# Imu_shield_v1.net
KiCad netlist of a schematic drawn in EAGLE
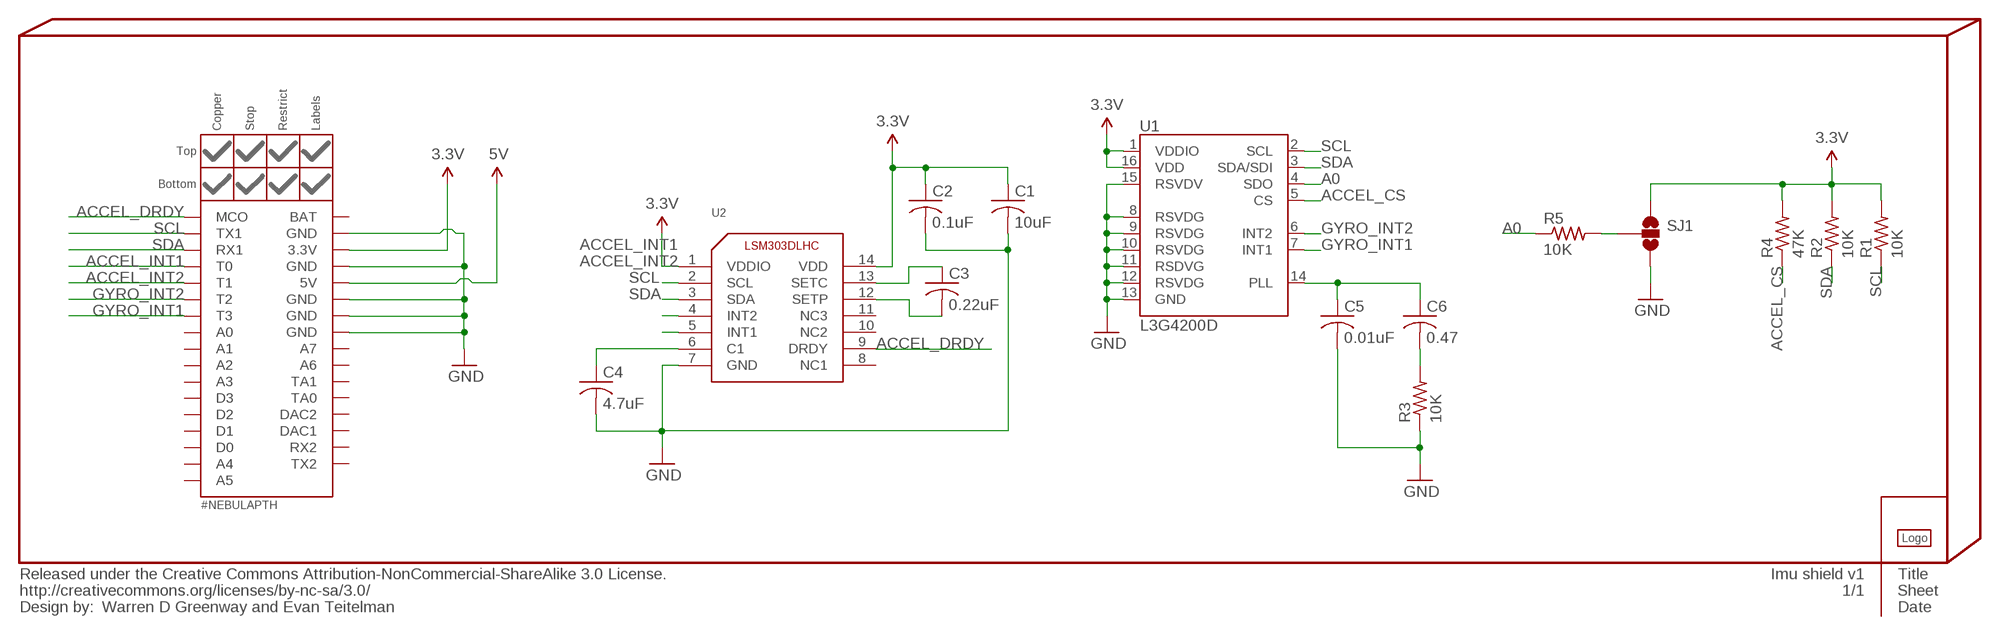
[diagram p0: schematic, sheet 1]

(export (version "E")
  (design (tool "Eeschema 10.0.6"))
  (components
    (comp (ref "C1")
      (value "10uF")
      (footprint "eagle-import:C0805")
      (libsource (lib "eagle-import") (part "C-USC0805"))
    )
    (comp (ref "C2")
      (value "0.1uF")
      (footprint "eagle-import:C0402")
      (libsource (lib "eagle-import") (part "C-USC0402"))
    )
    (comp (ref "C3")
      (value "0.22uF")
      (footprint "eagle-import:C0402")
      (libsource (lib "eagle-import") (part "C-USC0402"))
    )
    (comp (ref "C4")
      (value "4.7uF")
      (footprint "eagle-import:C0402")
      (libsource (lib "eagle-import") (part "C-USC0402"))
    )
    (comp (ref "C5")
      (value "0.01uF")
      (footprint "eagle-import:C0402")
      (libsource (lib "eagle-import") (part "C-USC0402"))
    )
    (comp (ref "C6")
      (value "0.47")
      (footprint "eagle-import:C0402")
      (libsource (lib "eagle-import") (part "C-USC0402"))
    )
    (comp (ref "INFO2")
      (value "Warren D Greenway and Evan Teitelman")
      (footprint "eagle-import:%CC-NC-SA")
      (libsource (lib "eagle-import") (part "%CC-NC-SA"))
    )
    (comp (ref "LOGO1")
      (value "#PYGMYLOGONORMAL")
      (footprint "eagle-import:#PYGMYLOGO")
      (libsource (lib "eagle-import") (part "#PYGMYLOGOLARGE"))
    )
    (comp (ref "NEBULA1")
      (value "#NEBULAPTH")
      (footprint "eagle-import:#NEBULA-PTH")
      (libsource (lib "eagle-import") (part "#NEBULAPTH"))
    )
    (comp (ref "NEBULAPART1")
      (value "#NEBULA-PARTLABELS-TOP")
      (footprint "eagle-import:#NEBULA-LABELS-TOP")
      (libsource (lib "eagle-import") (part "#NEBULA-PARTLABELS-TOP"))
    )
    (comp (ref "R1")
      (value "10K")
      (footprint "eagle-import:R0402")
      (libsource (lib "eagle-import") (part "R-US_R0402"))
    )
    (comp (ref "R2")
      (value "10K")
      (footprint "eagle-import:R0402")
      (libsource (lib "eagle-import") (part "R-US_R0402"))
    )
    (comp (ref "R3")
      (value "10K")
      (footprint "eagle-import:R0402")
      (libsource (lib "eagle-import") (part "R-US_R0402"))
    )
    (comp (ref "R4")
      (value "47K")
      (footprint "eagle-import:R0402")
      (libsource (lib "eagle-import") (part "R-US_R0402"))
    )
    (comp (ref "R5")
      (value "10K")
      (footprint "eagle-import:R0402")
      (libsource (lib "eagle-import") (part "R-US_R0402"))
    )
    (comp (ref "SJ1")
      (value "SOLDERJUMPER_2WAYPASTE1&2")
      (footprint "eagle-import:SJ_3_PASTE1&2")
      (libsource (lib "eagle-import") (part "SOLDERJUMPER_2WAYPASTE1&2"))
    )
    (comp (ref "U1")
      (value "L3G4200D")
      (footprint "eagle-import:LGA16-4X4")
      (libsource (lib "eagle-import") (part "L3G4200D"))
    )
    (comp (ref "U2")
      (value "FREESCALE-LSM303DLHC")
      (footprint "eagle-import:LGA14")
      (libsource (lib "eagle-import") (part "FREESCALE-LSM303DLHC"))
    )
  )
  (nets
    (net (code "1") (name "/A0") (class "Default")
      (node (ref "R5") (pin "1") (pinfunction "1_1") (pintype "passive"))
      (node (ref "U1") (pin "4") (pinfunction "SDO_4") (pintype "bidirectional"))
    )
    (net (code "2") (name "/ACCEL_CS") (class "Default")
      (node (ref "R4") (pin "1") (pinfunction "1_1") (pintype "passive"))
      (node (ref "U1") (pin "5") (pinfunction "CS_5") (pintype "bidirectional"))
    )
    (net (code "3") (name "/ACCEL_DRDY") (class "Default")
      (node (ref "NEBULA1") (pin "MCO") (pinfunction "MCO_MCO") (pintype "bidirectional"))
      (node (ref "U2") (pin "9") (pinfunction "DRDY_9") (pintype "bidirectional"))
    )
    (net (code "4") (name "/ACCEL_INT1") (class "Default")
      (node (ref "NEBULA1") (pin "T0") (pinfunction "T0_T0") (pintype "bidirectional"))
      (node (ref "U2") (pin "4") (pinfunction "INT2_4") (pintype "bidirectional"))
    )
    (net (code "5") (name "/ACCEL_INT2") (class "Default")
      (node (ref "NEBULA1") (pin "T1") (pinfunction "T1_T1") (pintype "bidirectional"))
      (node (ref "U2") (pin "5") (pinfunction "INT1_5") (pintype "bidirectional"))
    )
    (net (code "6") (name "/GYRO_INT1") (class "Default")
      (node (ref "NEBULA1") (pin "T3") (pinfunction "T3_T3") (pintype "bidirectional"))
      (node (ref "U1") (pin "7") (pinfunction "INT1_7") (pintype "bidirectional"))
    )
    (net (code "7") (name "/GYRO_INT2") (class "Default")
      (node (ref "NEBULA1") (pin "T2") (pinfunction "T2_T2") (pintype "bidirectional"))
      (node (ref "U1") (pin "6") (pinfunction "INT2_6") (pintype "bidirectional"))
    )
    (net (code "8") (name "/SCL") (class "Default")
      (node (ref "NEBULA1") (pin "COM1_TX") (pinfunction "TX1_COM1_TX") (pintype "bidirectional"))
      (node (ref "R1") (pin "1") (pinfunction "1_1") (pintype "passive"))
      (node (ref "U1") (pin "2") (pinfunction "SCL_2") (pintype "bidirectional"))
      (node (ref "U2") (pin "2") (pinfunction "SCL_2") (pintype "bidirectional"))
    )
    (net (code "9") (name "/SDA") (class "Default")
      (node (ref "NEBULA1") (pin "COM1_RX") (pinfunction "RX1_COM1_RX") (pintype "bidirectional"))
      (node (ref "R2") (pin "1") (pinfunction "1_1") (pintype "passive"))
      (node (ref "U1") (pin "3") (pinfunction "SDA/SDI_3") (pintype "bidirectional"))
      (node (ref "U2") (pin "3") (pinfunction "SDA_3") (pintype "bidirectional"))
    )
    (net (code "10") (name "@3.3V") (class "Default")
      (node (ref "C1") (pin "1") (pinfunction "1_1") (pintype "passive"))
      (node (ref "C2") (pin "1") (pinfunction "1_1") (pintype "passive"))
      (node (ref "NEBULA1") (pin "3.3V") (pinfunction "3.3V_3.3V") (pintype "bidirectional"))
      (node (ref "R1") (pin "2") (pinfunction "2_2") (pintype "passive"))
      (node (ref "R2") (pin "2") (pinfunction "2_2") (pintype "passive"))
      (node (ref "R4") (pin "2") (pinfunction "2_2") (pintype "passive"))
      (node (ref "SJ1") (pin "1") (pinfunction "1_1") (pintype "passive"))
      (node (ref "U1") (pin "1") (pinfunction "VDDIO_1") (pintype "bidirectional"))
      (node (ref "U1") (pin "16") (pinfunction "VDD_16") (pintype "bidirectional"))
      (node (ref "U2") (pin "1") (pinfunction "VDDIO_1") (pintype "bidirectional"))
      (node (ref "U2") (pin "14") (pinfunction "VDD_14") (pintype "bidirectional"))
    )
    (net (code "11") (name "@5V") (class "Default")
      (node (ref "NEBULA1") (pin "5V") (pinfunction "5V_5V") (pintype "bidirectional"))
    )
    (net (code "12") (name "@GND") (class "Default")
      (node (ref "C1") (pin "2") (pinfunction "2_2") (pintype "passive"))
      (node (ref "C2") (pin "2") (pinfunction "2_2") (pintype "passive"))
      (node (ref "C4") (pin "2") (pinfunction "2_2") (pintype "passive"))
      (node (ref "C5") (pin "2") (pinfunction "2_2") (pintype "passive"))
      (node (ref "NEBULA1") (pin "GND1") (pinfunction "GND_GND1") (pintype "bidirectional"))
      (node (ref "NEBULA1") (pin "GND2") (pinfunction "GND_GND2") (pintype "bidirectional"))
      (node (ref "NEBULA1") (pin "GND3") (pinfunction "GND_GND3") (pintype "bidirectional"))
      (node (ref "NEBULA1") (pin "GND4") (pinfunction "GND_GND4") (pintype "bidirectional"))
      (node (ref "NEBULA1") (pin "GND5") (pinfunction "GND_GND5") (pintype "bidirectional"))
      (node (ref "R3") (pin "1") (pinfunction "1_1") (pintype "passive"))
      (node (ref "SJ1") (pin "3") (pinfunction "3_3") (pintype "passive"))
      (node (ref "U1") (pin "10") (pinfunction "RSVDG_10") (pintype "bidirectional"))
      (node (ref "U1") (pin "11") (pinfunction "RSDVG_11") (pintype "bidirectional"))
      (node (ref "U1") (pin "12") (pinfunction "RSVDG_12") (pintype "bidirectional"))
      (node (ref "U1") (pin "13") (pinfunction "GND_13") (pintype "bidirectional"))
      (node (ref "U1") (pin "15") (pinfunction "RSVDV_15") (pintype "bidirectional"))
      (node (ref "U1") (pin "8") (pinfunction "RSVDG_8") (pintype "bidirectional"))
      (node (ref "U1") (pin "9") (pinfunction "RSVDG_9") (pintype "bidirectional"))
      (node (ref "U2") (pin "7") (pinfunction "GND_7") (pintype "bidirectional"))
    )
    (net (code "13") (name "Net-(C6-Pad2)") (class "Default")
      (node (ref "C6") (pin "2") (pinfunction "2_2") (pintype "passive"))
      (node (ref "R3") (pin "2") (pinfunction "2_2") (pintype "passive"))
    )
    (net (code "14") (name "Net-(R5-Pad2)") (class "Default")
      (node (ref "R5") (pin "2") (pinfunction "2_2") (pintype "passive"))
      (node (ref "SJ1") (pin "2") (pinfunction "2_2") (pintype "passive"))
    )
    (net (code "15") (name "Net-(U1-PLL)") (class "Default")
      (node (ref "C5") (pin "1") (pinfunction "1_1") (pintype "passive"))
      (node (ref "C6") (pin "1") (pinfunction "1_1") (pintype "passive"))
      (node (ref "U1") (pin "14") (pinfunction "PLL_14") (pintype "bidirectional"))
    )
    (net (code "16") (name "Net-(U2-C1)") (class "Default")
      (node (ref "C4") (pin "1") (pinfunction "1_1") (pintype "passive"))
      (node (ref "U2") (pin "6") (pinfunction "C1_6") (pintype "bidirectional"))
    )
    (net (code "17") (name "Net-(U2-SETC)") (class "Default")
      (node (ref "C3") (pin "1") (pinfunction "1_1") (pintype "passive"))
      (node (ref "U2") (pin "13") (pinfunction "SETC_13") (pintype "bidirectional"))
    )
    (net (code "18") (name "Net-(U2-SETP)") (class "Default")
      (node (ref "C3") (pin "2") (pinfunction "2_2") (pintype "passive"))
      (node (ref "U2") (pin "12") (pinfunction "SETP_12") (pintype "bidirectional"))
    )
    (net (code "19") (name "unconnected-(NEBULA1-PadA0)") (class "Default")
      (node (ref "NEBULA1") (pin "A0") (pinfunction "A0_A0") (pintype "bidirectional"))
    )
    (net (code "20") (name "unconnected-(NEBULA1-PadA1)") (class "Default")
      (node (ref "NEBULA1") (pin "A1") (pinfunction "A1_A1") (pintype "bidirectional"))
    )
    (net (code "21") (name "unconnected-(NEBULA1-PadA2)") (class "Default")
      (node (ref "NEBULA1") (pin "A2") (pinfunction "A2_A2") (pintype "bidirectional"))
    )
    (net (code "22") (name "unconnected-(NEBULA1-PadA3)") (class "Default")
      (node (ref "NEBULA1") (pin "A3") (pinfunction "A3_A3") (pintype "bidirectional"))
    )
    (net (code "23") (name "unconnected-(NEBULA1-PadA4)") (class "Default")
      (node (ref "NEBULA1") (pin "A4") (pinfunction "A4_A4") (pintype "bidirectional"))
    )
    (net (code "24") (name "unconnected-(NEBULA1-PadA5)") (class "Default")
      (node (ref "NEBULA1") (pin "A5") (pinfunction "A5_A5") (pintype "bidirectional"))
    )
    (net (code "25") (name "unconnected-(NEBULA1-PadA6)") (class "Default")
      (node (ref "NEBULA1") (pin "A6") (pinfunction "A6_A6") (pintype "bidirectional"))
    )
    (net (code "26") (name "unconnected-(NEBULA1-PadA7)") (class "Default")
      (node (ref "NEBULA1") (pin "A7") (pinfunction "A7_A7") (pintype "bidirectional"))
    )
    (net (code "27") (name "unconnected-(NEBULA1-PadBAT)") (class "Default")
      (node (ref "NEBULA1") (pin "BAT") (pinfunction "BAT_BAT") (pintype "bidirectional"))
    )
    (net (code "28") (name "unconnected-(NEBULA1-PadD0)") (class "Default")
      (node (ref "NEBULA1") (pin "D0") (pinfunction "D0_D0") (pintype "bidirectional"))
    )
    (net (code "29") (name "unconnected-(NEBULA1-PadD1)") (class "Default")
      (node (ref "NEBULA1") (pin "D1") (pinfunction "D1_D1") (pintype "bidirectional"))
    )
    (net (code "30") (name "unconnected-(NEBULA1-PadD2)") (class "Default")
      (node (ref "NEBULA1") (pin "D2") (pinfunction "D2_D2") (pintype "bidirectional"))
    )
    (net (code "31") (name "unconnected-(NEBULA1-PadD3)") (class "Default")
      (node (ref "NEBULA1") (pin "D3") (pinfunction "D3_D3") (pintype "bidirectional"))
    )
    (net (code "32") (name "unconnected-(NEBULA1-PadDAC1)") (class "Default")
      (node (ref "NEBULA1") (pin "DAC1") (pinfunction "DAC1_DAC1") (pintype "bidirectional"))
    )
    (net (code "33") (name "unconnected-(NEBULA1-PadDAC2)") (class "Default")
      (node (ref "NEBULA1") (pin "DAC2") (pinfunction "DAC2_DAC2") (pintype "bidirectional"))
    )
    (net (code "34") (name "unconnected-(NEBULA1-PadTA0)") (class "Default")
      (node (ref "NEBULA1") (pin "TA0") (pinfunction "TA0_TA0") (pintype "bidirectional"))
    )
    (net (code "35") (name "unconnected-(NEBULA1-PadTA1)") (class "Default")
      (node (ref "NEBULA1") (pin "TA1") (pinfunction "TA1_TA1") (pintype "bidirectional"))
    )
    (net (code "36") (name "unconnected-(NEBULA1-RX2-PadCOM2_RX)") (class "Default")
      (node (ref "NEBULA1") (pin "COM2_RX") (pinfunction "RX2_COM2_RX") (pintype "bidirectional"))
    )
    (net (code "37") (name "unconnected-(NEBULA1-TX2-PadCOM2_TX)") (class "Default")
      (node (ref "NEBULA1") (pin "COM2_TX") (pinfunction "TX2_COM2_TX") (pintype "bidirectional"))
    )
    (net (code "38") (name "unconnected-(U2-NC1-Pad8)") (class "Default")
      (node (ref "U2") (pin "8") (pinfunction "NC1_8") (pintype "bidirectional"))
    )
    (net (code "39") (name "unconnected-(U2-NC2-Pad10)") (class "Default")
      (node (ref "U2") (pin "10") (pinfunction "NC2_10") (pintype "bidirectional"))
    )
    (net (code "40") (name "unconnected-(U2-NC3-Pad11)") (class "Default")
      (node (ref "U2") (pin "11") (pinfunction "NC3_11") (pintype "bidirectional"))
    )
  )
)
